# Jacdac_Proto_Board.net
KiCad netlist of a schematic drawn in EAGLE
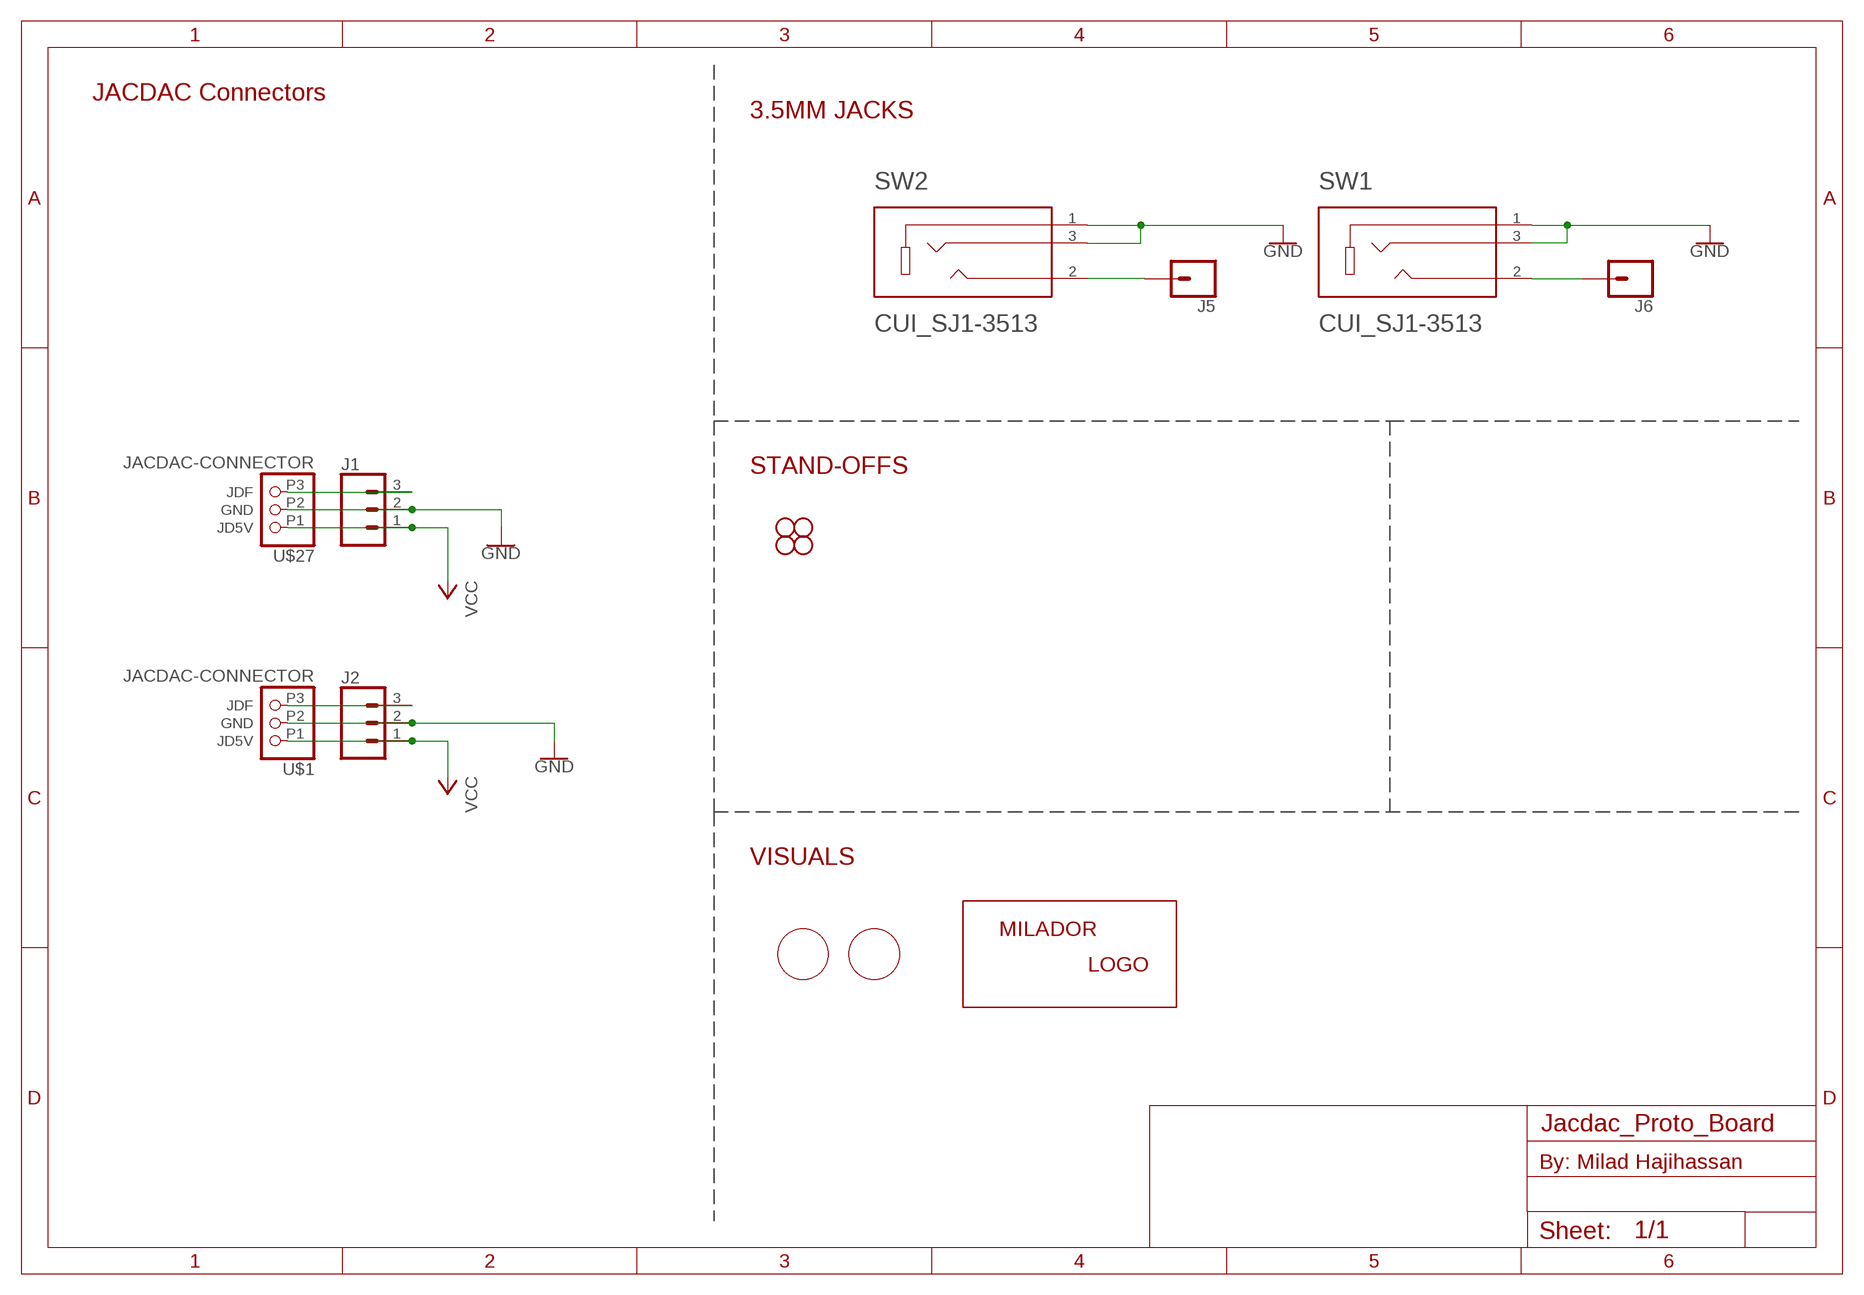
[diagram p0: schematic, sheet 1]

(export (version "E")
  (design (tool "Eeschema 10.0.6"))
  (components
    (comp (ref "H1")
      (value "STAND-OFF")
      (footprint "eagle-import:STAND-OFF")
      (libsource (lib "eagle-import") (part "SparkFun-Hardware_STAND-OFF"))
    )
    (comp (ref "H2")
      (value "STAND-OFF")
      (footprint "eagle-import:STAND-OFF")
      (libsource (lib "eagle-import") (part "SparkFun-Hardware_STAND-OFF"))
    )
    (comp (ref "J1")
      (value "CONNECTORS_CONN_03PTH")
      (footprint "eagle-import:CONNECTORS_1X03")
      (libsource (lib "eagle-import") (part "CONNECTORS_CONN_03PTH"))
    )
    (comp (ref "J2")
      (value "CONNECTORS_CONN_03PTH")
      (footprint "eagle-import:CONNECTORS_1X03")
      (libsource (lib "eagle-import") (part "CONNECTORS_CONN_03PTH"))
    )
    (comp (ref "J5")
      (value "CONNECTORS_CONN_01PTH_NO_SILK_YES_STOP")
      (footprint "eagle-import:CONNECTORS_1X01_NO_SILK")
      (libsource (lib "eagle-import") (part "CONNECTORS_CONN_01PTH_NO_SILK_YES_STOP"))
    )
    (comp (ref "J6")
      (value "CONNECTORS_CONN_01PTH_NO_SILK_YES_STOP")
      (footprint "eagle-import:CONNECTORS_1X01_NO_SILK")
      (libsource (lib "eagle-import") (part "CONNECTORS_CONN_01PTH_NO_SILK_YES_STOP"))
    )
    (comp (ref "JP3")
      (value "STAND-OFF")
      (footprint "eagle-import:STAND-OFF")
      (libsource (lib "eagle-import") (part "STAND-OFF"))
    )
    (comp (ref "JP4")
      (value "STAND-OFF")
      (footprint "eagle-import:STAND-OFF")
      (libsource (lib "eagle-import") (part "STAND-OFF"))
    )
    (comp (ref "SW1")
      (value "CUI_SJ1-3513")
      (footprint "eagle-import:CUI_SJ1-3513")
      (libsource (lib "eagle-import") (part "CUI_SJ1-3513"))
    )
    (comp (ref "SW2")
      (value "CUI_SJ1-3513")
      (footprint "eagle-import:CUI_SJ1-3513")
      (libsource (lib "eagle-import") (part "CUI_SJ1-3513"))
    )
    (comp (ref "U$1")
      (value "JACDAC-CONNECTOR")
      (footprint "eagle-import:JACDAC-CONNECTOR")
      (libsource (lib "eagle-import") (part "JACDAC-CONNECTOR"))
    )
    (comp (ref "U$2")
      (value "MILADOR-LOGO-")
      (footprint "eagle-import:MILADOR_LOGO1")
      (libsource (lib "eagle-import") (part "MILADOR-LOGO-"))
    )
    (comp (ref "U$17")
      (value "MILADOR-SWITCH-NAME-SW1")
      (footprint "eagle-import:SWITCH-SW1")
      (libsource (lib "eagle-import") (part "MILADOR-SWITCH-NAME-SW1"))
    )
    (comp (ref "U$18")
      (value "MILADOR-SWITCH-NAME-SW2")
      (footprint "eagle-import:SWITCH-SW2")
      (libsource (lib "eagle-import") (part "MILADOR-SWITCH-NAME-SW2"))
    )
    (comp (ref "U$27")
      (value "JACDAC-CONNECTOR")
      (footprint "eagle-import:JACDAC-CONNECTOR")
      (libsource (lib "eagle-import") (part "JACDAC-CONNECTOR"))
    )
  )
  (nets
    (net (code "1") (name "GND") (class "Default")
      (node (ref "J1") (pin "2") (pinfunction "2_2") (pintype "passive"))
      (node (ref "J2") (pin "2") (pinfunction "2_2") (pintype "passive"))
      (node (ref "SW1") (pin "1") (pinfunction "1_1") (pintype "passive"))
      (node (ref "SW1") (pin "3") (pinfunction "3_3") (pintype "passive"))
      (node (ref "SW2") (pin "1") (pinfunction "1_1") (pintype "passive"))
      (node (ref "SW2") (pin "3") (pinfunction "3_3") (pintype "passive"))
      (node (ref "U$1") (pin "P2") (pinfunction "GND_P2") (pintype "passive"))
      (node (ref "U$27") (pin "P2") (pinfunction "GND_P2") (pintype "passive"))
    )
    (net (code "2") (name "Net-(J5-Pad1)") (class "Default")
      (node (ref "J5") (pin "1") (pinfunction "1_1") (pintype "passive"))
      (node (ref "SW2") (pin "2") (pinfunction "2_2") (pintype "passive"))
    )
    (net (code "3") (name "Net-(J6-Pad1)") (class "Default")
      (node (ref "J6") (pin "1") (pinfunction "1_1") (pintype "passive"))
      (node (ref "SW1") (pin "2") (pinfunction "2_2") (pintype "passive"))
    )
    (net (code "4") (name "Net-(U$1-JDF)") (class "Default")
      (node (ref "J2") (pin "3") (pinfunction "3_3") (pintype "passive"))
      (node (ref "U$1") (pin "P3") (pinfunction "JDF_P3") (pintype "passive"))
    )
    (net (code "5") (name "Net-(U$27-JDF)") (class "Default")
      (node (ref "J1") (pin "3") (pinfunction "3_3") (pintype "passive"))
      (node (ref "U$27") (pin "P3") (pinfunction "JDF_P3") (pintype "passive"))
    )
    (net (code "6") (name "VCC") (class "Default")
      (node (ref "J1") (pin "1") (pinfunction "1_1") (pintype "passive"))
      (node (ref "J2") (pin "1") (pinfunction "1_1") (pintype "passive"))
      (node (ref "U$1") (pin "P1") (pinfunction "JD5V_P1") (pintype "passive"))
      (node (ref "U$27") (pin "P1") (pinfunction "JD5V_P1") (pintype "passive"))
    )
  )
)
